# Filter.net
KiCad netlist of a schematic drawn in Altium Designer
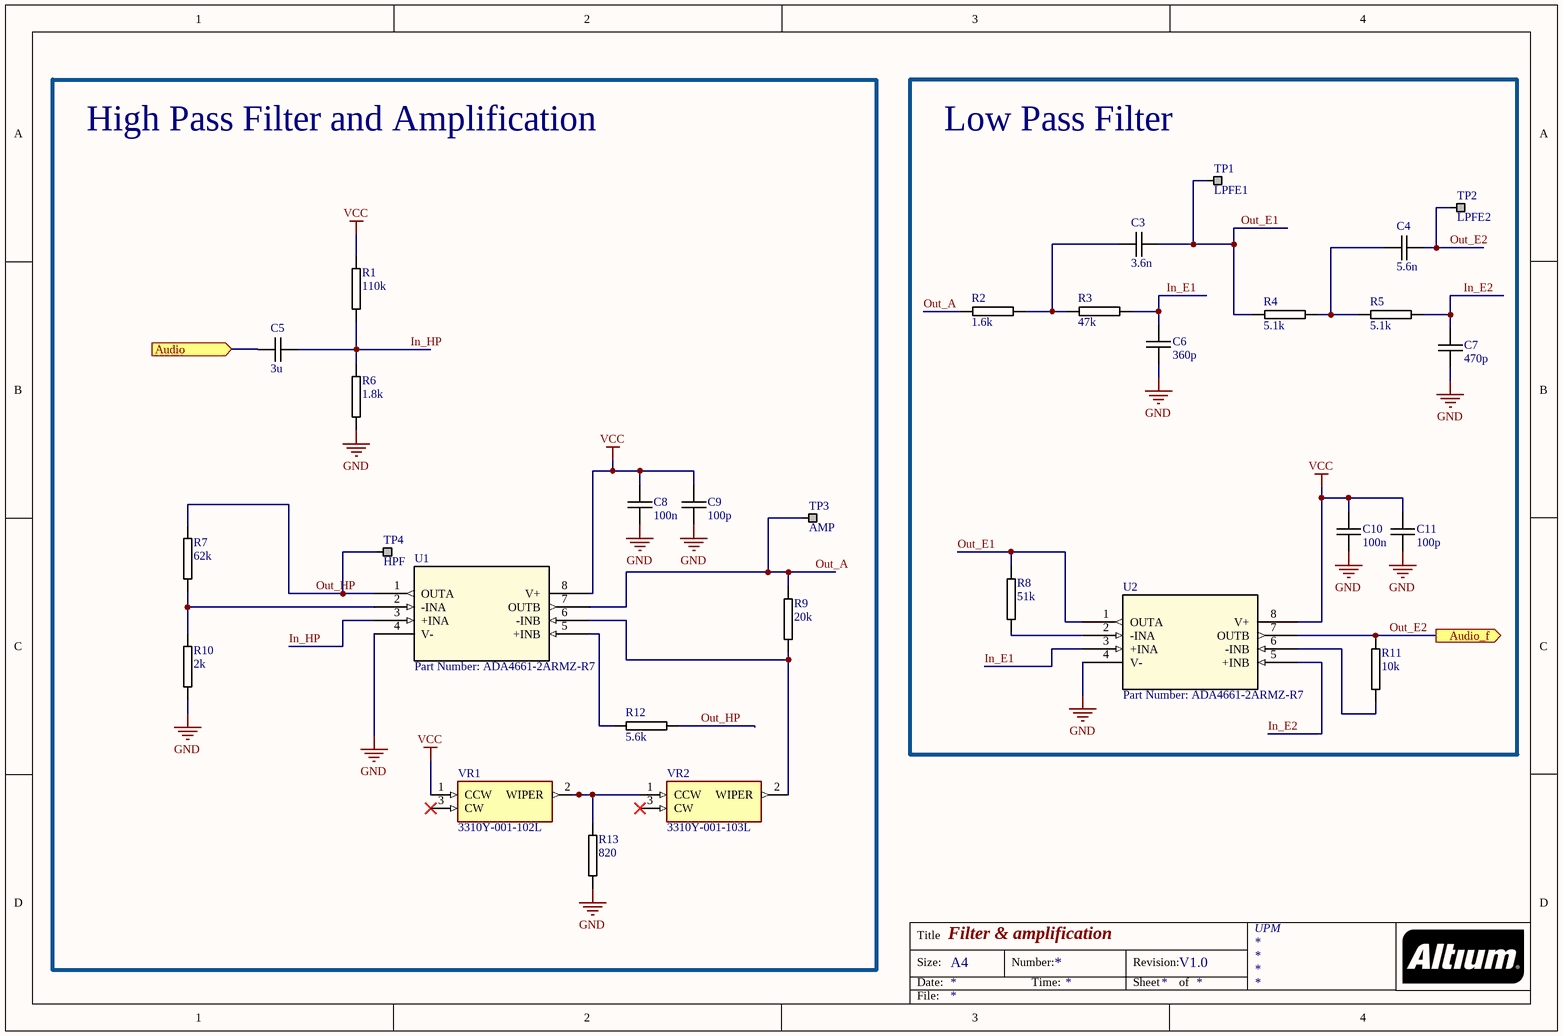
[diagram p0: Filter.SchDoc]

(export (version "E")
  (design (tool "Eeschema 10.0.6"))
  (components
    (comp (ref "C3")
      (value "3.6n")
      (footprint "0805C-GENERIC")
      (description "GENERIC CAPACITOR NON POLARISED0603")
      (libsource (lib "vh_altium_library") (part "C0805-GENERIC"))
    )
    (comp (ref "C4")
      (value "5.6n")
      (footprint "0805C-GENERIC")
      (description "GENERIC CAPACITOR NON POLARISED0603")
      (libsource (lib "vh_altium_library") (part "C0805-GENERIC"))
    )
    (comp (ref "C5")
      (value "3u")
      (footprint "0805C-GENERIC")
      (description "GENERIC CAPACITOR NON POLARISED0603")
      (libsource (lib "vh_altium_library") (part "C0805-GENERIC"))
    )
    (comp (ref "C6")
      (value "360p")
      (footprint "0805C-GENERIC")
      (description "GENERIC CAPACITOR NON POLARISED0603")
      (libsource (lib "vh_altium_library") (part "C0805-GENERIC"))
    )
    (comp (ref "C7")
      (value "470p")
      (footprint "0805C-GENERIC")
      (description "GENERIC CAPACITOR NON POLARISED0603")
      (libsource (lib "vh_altium_library") (part "C0805-GENERIC"))
    )
    (comp (ref "C8")
      (value "100n")
      (footprint "0805C-GENERIC")
      (description "GENERIC CAPACITOR NON POLARISED0603")
      (libsource (lib "vh_altium_library") (part "C0805-GENERIC"))
    )
    (comp (ref "C9")
      (value "100p")
      (footprint "0805C-GENERIC")
      (description "GENERIC CAPACITOR NON POLARISED0603")
      (libsource (lib "vh_altium_library") (part "C0805-GENERIC"))
    )
    (comp (ref "C10")
      (value "100n")
      (footprint "0805C-GENERIC")
      (description "GENERIC CAPACITOR NON POLARISED0603")
      (libsource (lib "vh_altium_library") (part "C0805-GENERIC"))
    )
    (comp (ref "C11")
      (value "100p")
      (footprint "0805C-GENERIC")
      (description "GENERIC CAPACITOR NON POLARISED0603")
      (libsource (lib "vh_altium_library") (part "C0805-GENERIC"))
    )
    (comp (ref "R1")
      (value "110k")
      (footprint "0805R-GENERIC")
      (description "GENERIC RESISTOR 0805")
      (libsource (lib "vh_altium_library") (part "R0805-GENERIC"))
    )
    (comp (ref "R2")
      (value "1.6k")
      (footprint "0805R-GENERIC")
      (description "GENERIC RESISTOR 0805")
      (libsource (lib "vh_altium_library") (part "R0805-GENERIC"))
    )
    (comp (ref "R3")
      (value "47k")
      (footprint "0805R-GENERIC")
      (description "GENERIC RESISTOR 0805")
      (libsource (lib "vh_altium_library") (part "R0805-GENERIC"))
    )
    (comp (ref "R4")
      (value "5.1k")
      (footprint "0805R-GENERIC")
      (description "GENERIC RESISTOR 0805")
      (libsource (lib "vh_altium_library") (part "R0805-GENERIC"))
    )
    (comp (ref "R5")
      (value "5.1k")
      (footprint "0805R-GENERIC")
      (description "GENERIC RESISTOR 0805")
      (libsource (lib "vh_altium_library") (part "R0805-GENERIC"))
    )
    (comp (ref "R6")
      (value "1.8k")
      (footprint "0805R-GENERIC")
      (description "GENERIC RESISTOR 0805")
      (libsource (lib "vh_altium_library") (part "R0805-GENERIC"))
    )
    (comp (ref "R7")
      (value "62k")
      (footprint "0805R-GENERIC")
      (description "GENERIC RESISTOR 0805")
      (libsource (lib "vh_altium_library") (part "R0805-GENERIC"))
    )
    (comp (ref "R8")
      (value "51k")
      (footprint "0805R-GENERIC")
      (description "GENERIC RESISTOR 0805")
      (libsource (lib "vh_altium_library") (part "R0805-GENERIC"))
    )
    (comp (ref "R9")
      (value "20k")
      (footprint "0805R-GENERIC")
      (description "GENERIC RESISTOR 0805")
      (libsource (lib "vh_altium_library") (part "R0805-GENERIC"))
    )
    (comp (ref "R10")
      (value "2k")
      (footprint "0805R-GENERIC")
      (description "GENERIC RESISTOR 0805")
      (libsource (lib "vh_altium_library") (part "R0805-GENERIC"))
    )
    (comp (ref "R11")
      (value "10k")
      (footprint "0805R-GENERIC")
      (description "GENERIC RESISTOR 0805")
      (libsource (lib "vh_altium_library") (part "R0805-GENERIC"))
    )
    (comp (ref "R12")
      (value "5.6k")
      (footprint "0805R-GENERIC")
      (description "GENERIC RESISTOR 0805")
      (libsource (lib "vh_altium_library") (part "R0805-GENERIC"))
    )
    (comp (ref "R13")
      (value "820")
      (footprint "0805R-GENERIC")
      (description "GENERIC RESISTOR 0805")
      (libsource (lib "vh_altium_library") (part "R0805-GENERIC"))
    )
    (comp (ref "TP1")
      (value "LPFE1")
      (footprint "TESTPIN")
      (description "TESTPIN SINGLE PIN HEADER")
      (libsource (lib "vh_altium_library") (part "TESTPIN"))
    )
    (comp (ref "TP2")
      (value "LPFE2")
      (footprint "TESTPIN")
      (description "TESTPIN SINGLE PIN HEADER")
      (libsource (lib "vh_altium_library") (part "TESTPIN"))
    )
    (comp (ref "TP3")
      (value "AMP")
      (footprint "TESTPIN")
      (description "TESTPIN SINGLE PIN HEADER")
      (libsource (lib "vh_altium_library") (part "TESTPIN"))
    )
    (comp (ref "TP4")
      (value "HPF")
      (footprint "TESTPIN")
      (description "TESTPIN SINGLE PIN HEADER")
      (libsource (lib "vh_altium_library") (part "TESTPIN"))
    )
    (comp (ref "U1")
      (value "Part Number: ADA4661-2ARMZ-R7")
      (footprint "RM_8")
      (description "No Description Available")
      (fields
        (field (name "MANUFACTURER_PART_NUMBER") "ADA4661-2ARMZ-R7")
        (field (name "COPYRIGHT") "Copyright (C) 2016 Accelerated Designs. All rights reserved")
      )
      (libsource (lib "2020-03-25_06-16-48") (part "ADA4661-2ARMZ-R7"))
    )
    (comp (ref "U2")
      (value "Part Number: ADA4661-2ARMZ-R7")
      (footprint "RM_8")
      (description "No Description Available")
      (fields
        (field (name "MANUFACTURER_PART_NUMBER") "ADA4661-2ARMZ-R7")
        (field (name "COPYRIGHT") "Copyright (C) 2016 Accelerated Designs. All rights reserved")
      )
      (libsource (lib "2020-03-25_06-16-48") (part "ADA4661-2ARMZ-R7"))
    )
    (comp (ref "VR1")
      (value "3310Y-001-102L")
      (footprint "3310Y-001")
      (description "Variable Resistor")
      (fields
        (field (name "MANUFACTURER_PART_NUMBER") "3310Y-001-103L")
        (field (name "MOUSER PART NUMBER") "652-3310Y-001-103L")
      )
      (libsource (lib "PMOD") (part "3310Y-001-103L"))
    )
    (comp (ref "VR2")
      (value "3310Y-001-103L")
      (footprint "3310Y-001")
      (description "Variable Resistor")
      (fields
        (field (name "MOUSER PART NUMBER") "652-3310Y-001-103L")
        (field (name "RS PART NUMBER") "5220625P")
      )
      (libsource (lib "PMOD") (part "3310Y-001-103L"))
    )
  )
  (nets
    (net (code "1") (name "/Audio") (class "Default") (node (ref "C5") (pin "1") (pintype "passive")))
    (net (code "2") (name "/In_E1") (class "Default")
      (node (ref "C6") (pin "2") (pintype "passive"))
      (node (ref "R3") (pin "2") (pintype "passive"))
      (node (ref "U2") (pin "3") (pinfunction "+INA_3") (pintype "input"))
    )
    (net (code "3") (name "/In_E2") (class "Default")
      (node (ref "C7") (pin "2") (pintype "passive"))
      (node (ref "R5") (pin "2") (pintype "passive"))
      (node (ref "U2") (pin "5") (pinfunction "+INB_5") (pintype "input"))
    )
    (net (code "4") (name "/In_HP") (class "Default")
      (node (ref "C5") (pin "2") (pintype "passive"))
      (node (ref "R1") (pin "2") (pintype "passive"))
      (node (ref "R6") (pin "1") (pintype "passive"))
      (node (ref "U1") (pin "3") (pinfunction "+INA_3") (pintype "input"))
    )
    (net (code "5") (name "/Out_A") (class "Default")
      (node (ref "R2") (pin "1") (pintype "passive"))
      (node (ref "R9") (pin "1") (pintype "passive"))
      (node (ref "TP3") (pin "1") (pinfunction "1_1") (pintype "passive"))
      (node (ref "U1") (pin "7") (pinfunction "OUTB_7") (pintype "output"))
    )
    (net (code "6") (name "/Out_E1") (class "Default")
      (node (ref "C3") (pin "2") (pintype "passive"))
      (node (ref "R4") (pin "1") (pintype "passive"))
      (node (ref "R8") (pin "1") (pintype "passive"))
      (node (ref "TP1") (pin "1") (pinfunction "1_1") (pintype "passive"))
      (node (ref "U2") (pin "1") (pinfunction "OUTA_1") (pintype "output"))
    )
    (net (code "7") (name "/Out_E2") (class "Default")
      (node (ref "C4") (pin "2") (pintype "passive"))
      (node (ref "R11") (pin "1") (pintype "passive"))
      (node (ref "TP2") (pin "1") (pinfunction "1_1") (pintype "passive"))
      (node (ref "U2") (pin "7") (pinfunction "OUTB_7") (pintype "output"))
    )
    (net (code "8") (name "/Out_HP") (class "Default")
      (node (ref "R12") (pin "2") (pintype "passive"))
      (node (ref "R7") (pin "1") (pintype "passive"))
      (node (ref "TP4") (pin "1") (pinfunction "1_1") (pintype "passive"))
      (node (ref "U1") (pin "1") (pinfunction "OUTA_1") (pintype "output"))
    )
    (net (code "9") (name "GND") (class "Default")
      (node (ref "C10") (pin "2") (pintype "passive"))
      (node (ref "C11") (pin "2") (pintype "passive"))
      (node (ref "C6") (pin "1") (pintype "passive"))
      (node (ref "C7") (pin "1") (pintype "passive"))
      (node (ref "C8") (pin "2") (pintype "passive"))
      (node (ref "C9") (pin "2") (pintype "passive"))
      (node (ref "R10") (pin "2") (pintype "passive"))
      (node (ref "R13") (pin "2") (pintype "passive"))
      (node (ref "R6") (pin "2") (pintype "passive"))
      (node (ref "U1") (pin "4") (pinfunction "V-_4") (pintype "power_in"))
      (node (ref "U2") (pin "4") (pinfunction "V-_4") (pintype "power_in"))
    )
    (net (code "10") (name "Net-(C3-Pad1)") (class "Default")
      (node (ref "C3") (pin "1") (pintype "passive"))
      (node (ref "R2") (pin "2") (pintype "passive"))
      (node (ref "R3") (pin "1") (pintype "passive"))
    )
    (net (code "11") (name "Net-(C4-Pad1)") (class "Default")
      (node (ref "C4") (pin "1") (pintype "passive"))
      (node (ref "R4") (pin "2") (pintype "passive"))
      (node (ref "R5") (pin "1") (pintype "passive"))
    )
    (net (code "12") (name "Net-(U1-+INB)") (class "Default")
      (node (ref "R12") (pin "1") (pintype "passive"))
      (node (ref "U1") (pin "5") (pinfunction "+INB_5") (pintype "input"))
    )
    (net (code "13") (name "Net-(U1--INA)") (class "Default")
      (node (ref "R10") (pin "1") (pintype "passive"))
      (node (ref "R7") (pin "2") (pintype "passive"))
      (node (ref "U1") (pin "2") (pinfunction "-INA_2") (pintype "input"))
    )
    (net (code "14") (name "Net-(U1--INB)") (class "Default")
      (node (ref "R9") (pin "2") (pintype "passive"))
      (node (ref "U1") (pin "6") (pinfunction "-INB_6") (pintype "input"))
      (node (ref "VR2") (pin "2") (pinfunction "WIPER_2") (pintype "output"))
    )
    (net (code "15") (name "Net-(U2--INA)") (class "Default")
      (node (ref "R8") (pin "2") (pintype "passive"))
      (node (ref "U2") (pin "2") (pinfunction "-INA_2") (pintype "input"))
    )
    (net (code "16") (name "Net-(U2--INB)") (class "Default")
      (node (ref "R11") (pin "2") (pintype "passive"))
      (node (ref "U2") (pin "6") (pinfunction "-INB_6") (pintype "input"))
    )
    (net (code "17") (name "Net-(VR1-WIPER)") (class "Default")
      (node (ref "R13") (pin "1") (pintype "passive"))
      (node (ref "VR1") (pin "2") (pinfunction "WIPER_2") (pintype "output"))
      (node (ref "VR2") (pin "1") (pinfunction "CCW_1") (pintype "input"))
    )
    (net (code "18") (name "VCC") (class "Default")
      (node (ref "C10") (pin "1") (pintype "passive"))
      (node (ref "C11") (pin "1") (pintype "passive"))
      (node (ref "C8") (pin "1") (pintype "passive"))
      (node (ref "C9") (pin "1") (pintype "passive"))
      (node (ref "R1") (pin "1") (pintype "passive"))
      (node (ref "U1") (pin "8") (pinfunction "V+_8") (pintype "power_in"))
      (node (ref "U2") (pin "8") (pinfunction "V+_8") (pintype "power_in"))
      (node (ref "VR1") (pin "1") (pinfunction "CCW_1") (pintype "input"))
    )
    (net (code "19") (name "unconnected-(VR1-CW-Pad3)") (class "Default")
      (node (ref "VR1") (pin "3") (pinfunction "CW_3") (pintype "input+no_connect"))
    )
    (net (code "20") (name "unconnected-(VR2-CW-Pad3)") (class "Default")
      (node (ref "VR2") (pin "3") (pinfunction "CW_3") (pintype "input+no_connect"))
    )
  )
)
